# Sheet5.net
KiCad netlist of a schematic drawn in Altium Designer
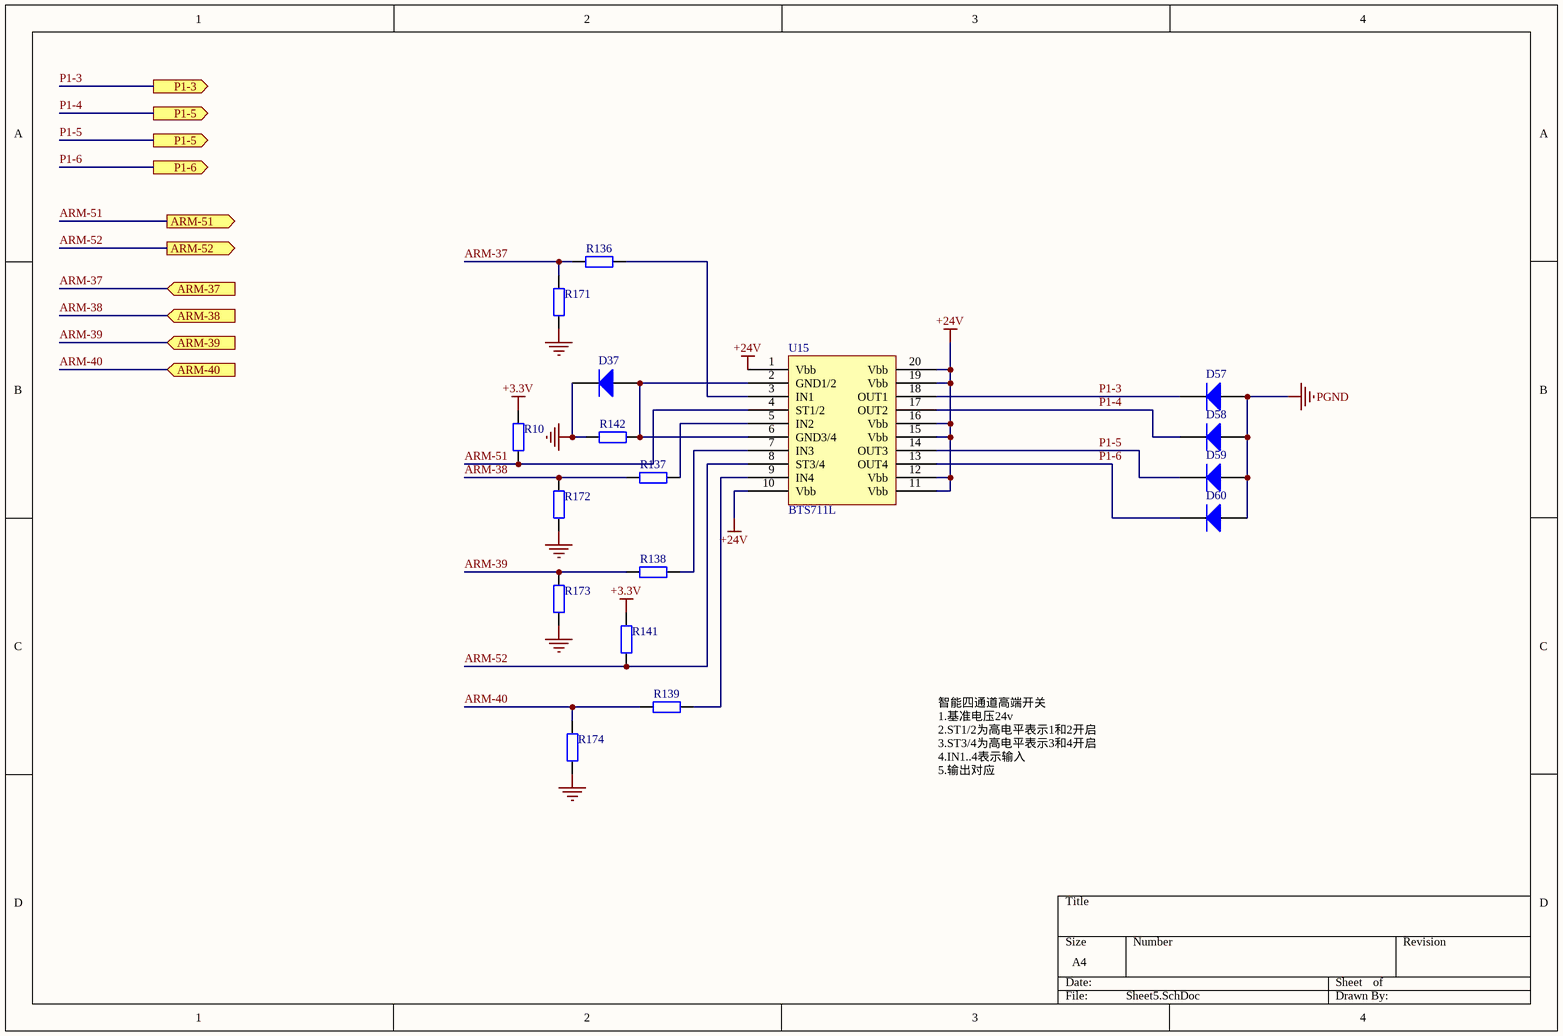
[diagram p0: Sheet5.SchDoc]

(export (version "E")
  (design (tool "Eeschema 10.0.6"))
  (components
    (comp (ref "D37")
      (value "Diode 1N4007")
      (footprint "DO-41")
      (description "1 Amp General Purpose Rectifier")
      (fields (field (name "PUBLISHER") "Altium Limited"))
      (libsource (lib "Miscellaneous Devices") (part "Diode 1N4007"))
    )
    (comp (ref "D57")
      (value "Diode 1N4007")
      (footprint "DO-41")
      (description "1 Amp General Purpose Rectifier")
      (fields (field (name "PUBLISHER") "Altium Limited"))
      (libsource (lib "Miscellaneous Devices") (part "Diode 1N4007"))
    )
    (comp (ref "D58")
      (value "Diode 1N4007")
      (footprint "DO-41")
      (description "1 Amp General Purpose Rectifier")
      (fields (field (name "PUBLISHER") "Altium Limited"))
      (libsource (lib "Miscellaneous Devices") (part "Diode 1N4007"))
    )
    (comp (ref "D59")
      (value "Diode 1N4007")
      (footprint "DO-41")
      (description "1 Amp General Purpose Rectifier")
      (fields (field (name "PUBLISHER") "Altium Limited"))
      (libsource (lib "Miscellaneous Devices") (part "Diode 1N4007"))
    )
    (comp (ref "D60")
      (value "Diode 1N4007")
      (footprint "DO-41")
      (description "1 Amp General Purpose Rectifier")
      (fields (field (name "PUBLISHER") "Altium Limited"))
      (libsource (lib "Miscellaneous Devices") (part "Diode 1N4007"))
    )
    (comp (ref "R10")
      (value "Res2")
      (footprint "AXIAL-0.4")
      (description "Resistor")
      (fields (field (name "PUBLISHER") "Altium Limited"))
      (libsource (lib "Miscellaneous Devices") (part "Res2"))
    )
    (comp (ref "R136")
      (value "Res2")
      (footprint "AXIAL-0.4")
      (description "Resistor")
      (fields (field (name "PUBLISHER") "Altium Limited"))
      (libsource (lib "") (part "Res2_1"))
    )
    (comp (ref "R137")
      (value "Res2")
      (footprint "AXIAL-0.4")
      (description "Resistor")
      (fields (field (name "PUBLISHER") "Altium Limited"))
      (libsource (lib "") (part "Res2_1"))
    )
    (comp (ref "R138")
      (value "Res2")
      (footprint "AXIAL-0.4")
      (description "Resistor")
      (fields (field (name "PUBLISHER") "Altium Limited"))
      (libsource (lib "") (part "Res2_1"))
    )
    (comp (ref "R139")
      (value "Res2")
      (footprint "AXIAL-0.4")
      (description "Resistor")
      (fields (field (name "PUBLISHER") "Altium Limited"))
      (libsource (lib "") (part "Res2_2"))
    )
    (comp (ref "R141")
      (value "Res2")
      (footprint "AXIAL-0.4")
      (description "Resistor")
      (fields (field (name "PUBLISHER") "Altium Limited"))
      (libsource (lib "Miscellaneous Devices") (part "Res2"))
    )
    (comp (ref "R142")
      (value "Res2")
      (footprint "AXIAL-0.4")
      (description "Resistor")
      (fields (field (name "PUBLISHER") "Altium Limited"))
      (libsource (lib "") (part "Res2_1"))
    )
    (comp (ref "R171")
      (value "Res2")
      (footprint "AXIAL-0.4")
      (description "Resistor")
      (fields (field (name "PUBLISHER") "Altium Limited"))
      (libsource (lib "Miscellaneous Devices") (part "Res2"))
    )
    (comp (ref "R172")
      (value "Res2")
      (footprint "AXIAL-0.4")
      (description "Resistor")
      (fields (field (name "PUBLISHER") "Altium Limited"))
      (libsource (lib "Miscellaneous Devices") (part "Res2"))
    )
    (comp (ref "R173")
      (value "Res2")
      (footprint "AXIAL-0.4")
      (description "Resistor")
      (fields (field (name "PUBLISHER") "Altium Limited"))
      (libsource (lib "Miscellaneous Devices") (part "Res2"))
    )
    (comp (ref "R174")
      (value "Res2")
      (footprint "AXIAL-0.4")
      (description "Resistor")
      (fields (field (name "PUBLISHER") "Altium Limited"))
      (libsource (lib "Miscellaneous Devices") (part "Res2"))
    )
    (comp (ref "U15") (value "BTS711L") (libsource (lib "BTS711L1") (part "Component_1")))
  )
  (nets
    (net (code "1") (name "+3.3V") (class "Default")
      (node (ref "R10") (pin "2") (pinfunction "2_2") (pintype "passive"))
      (node (ref "R141") (pin "2") (pinfunction "2_2") (pintype "passive"))
    )
    (net (code "2") (name "+24V") (class "Default")
      (node (ref "U15") (pin "1") (pinfunction "Vbb_1") (pintype "passive"))
      (node (ref "U15") (pin "10") (pinfunction "Vbb_10") (pintype "passive"))
      (node (ref "U15") (pin "11") (pinfunction "Vbb_11") (pintype "passive"))
      (node (ref "U15") (pin "12") (pinfunction "Vbb_12") (pintype "passive"))
      (node (ref "U15") (pin "15") (pinfunction "Vbb_15") (pintype "passive"))
      (node (ref "U15") (pin "16") (pinfunction "Vbb_16") (pintype "passive"))
      (node (ref "U15") (pin "19") (pinfunction "Vbb_19") (pintype "passive"))
      (node (ref "U15") (pin "20") (pinfunction "Vbb_20") (pintype "passive"))
    )
    (net (code "3") (name "/ARM-37") (class "Default")
      (node (ref "R136") (pin "1") (pinfunction "1_1") (pintype "passive"))
      (node (ref "R171") (pin "2") (pinfunction "2_2") (pintype "passive"))
    )
    (net (code "4") (name "/ARM-38") (class "Default")
      (node (ref "R137") (pin "1") (pinfunction "1_1") (pintype "passive"))
      (node (ref "R172") (pin "2") (pinfunction "2_2") (pintype "passive"))
    )
    (net (code "5") (name "/ARM-39") (class "Default")
      (node (ref "R138") (pin "1") (pinfunction "1_1") (pintype "passive"))
      (node (ref "R173") (pin "2") (pinfunction "2_2") (pintype "passive"))
    )
    (net (code "6") (name "/ARM-40") (class "Default")
      (node (ref "R139") (pin "2") (pinfunction "2_2") (pintype "passive"))
      (node (ref "R174") (pin "2") (pinfunction "2_2") (pintype "passive"))
    )
    (net (code "7") (name "/ARM-51") (class "Default")
      (node (ref "R10") (pin "1") (pinfunction "1_1") (pintype "passive"))
      (node (ref "U15") (pin "4") (pinfunction "ST1/2_4") (pintype "passive"))
    )
    (net (code "8") (name "/ARM-52") (class "Default")
      (node (ref "R141") (pin "1") (pinfunction "1_1") (pintype "passive"))
      (node (ref "U15") (pin "8") (pinfunction "ST3/4_8") (pintype "passive"))
    )
    (net (code "9") (name "/P1-3") (class "Default")
      (node (ref "D57") (pin "2") (pinfunction "K_2") (pintype "passive"))
      (node (ref "U15") (pin "18") (pinfunction "OUT1_18") (pintype "passive"))
    )
    (net (code "10") (name "/P1-4") (class "Default")
      (node (ref "D58") (pin "2") (pinfunction "K_2") (pintype "passive"))
      (node (ref "D59") (pin "2") (pinfunction "K_2") (pintype "passive"))
      (node (ref "U15") (pin "14") (pinfunction "OUT3_14") (pintype "passive"))
      (node (ref "U15") (pin "17") (pinfunction "OUT2_17") (pintype "passive"))
    )
    (net (code "11") (name "/P1-6") (class "Default")
      (node (ref "D60") (pin "2") (pinfunction "K_2") (pintype "passive"))
      (node (ref "U15") (pin "13") (pinfunction "OUT4_13") (pintype "passive"))
    )
    (net (code "12") (name "GND") (class "Default")
      (node (ref "D37") (pin "2") (pinfunction "K_2") (pintype "passive"))
      (node (ref "R142") (pin "1") (pinfunction "1_1") (pintype "passive"))
      (node (ref "R171") (pin "1") (pinfunction "1_1") (pintype "passive"))
      (node (ref "R172") (pin "1") (pinfunction "1_1") (pintype "passive"))
      (node (ref "R173") (pin "1") (pinfunction "1_1") (pintype "passive"))
      (node (ref "R174") (pin "1") (pinfunction "1_1") (pintype "passive"))
    )
    (net (code "13") (name "Net-(D37-A)") (class "Default")
      (node (ref "D37") (pin "1") (pinfunction "A_1") (pintype "passive"))
      (node (ref "R142") (pin "2") (pinfunction "2_2") (pintype "passive"))
      (node (ref "U15") (pin "2") (pinfunction "GND1/2_2") (pintype "passive"))
      (node (ref "U15") (pin "6") (pinfunction "GND3/4_6") (pintype "passive"))
    )
    (net (code "14") (name "Net-(U15-IN1)") (class "Default")
      (node (ref "R136") (pin "2") (pinfunction "2_2") (pintype "passive"))
      (node (ref "U15") (pin "3") (pinfunction "IN1_3") (pintype "passive"))
    )
    (net (code "15") (name "Net-(U15-IN2)") (class "Default")
      (node (ref "R137") (pin "2") (pinfunction "2_2") (pintype "passive"))
      (node (ref "U15") (pin "5") (pinfunction "IN2_5") (pintype "passive"))
    )
    (net (code "16") (name "Net-(U15-IN3)") (class "Default")
      (node (ref "R138") (pin "2") (pinfunction "2_2") (pintype "passive"))
      (node (ref "U15") (pin "7") (pinfunction "IN3_7") (pintype "passive"))
    )
    (net (code "17") (name "Net-(U15-IN4)") (class "Default")
      (node (ref "R139") (pin "1") (pinfunction "1_1") (pintype "passive"))
      (node (ref "U15") (pin "9") (pinfunction "IN4_9") (pintype "passive"))
    )
    (net (code "18") (name "PGND") (class "Default")
      (node (ref "D57") (pin "1") (pinfunction "A_1") (pintype "passive"))
      (node (ref "D58") (pin "1") (pinfunction "A_1") (pintype "passive"))
      (node (ref "D59") (pin "1") (pinfunction "A_1") (pintype "passive"))
      (node (ref "D60") (pin "1") (pinfunction "A_1") (pintype "passive"))
    )
  )
)
